# -Power.net
KiCad netlist of a schematic drawn in Altium Designer
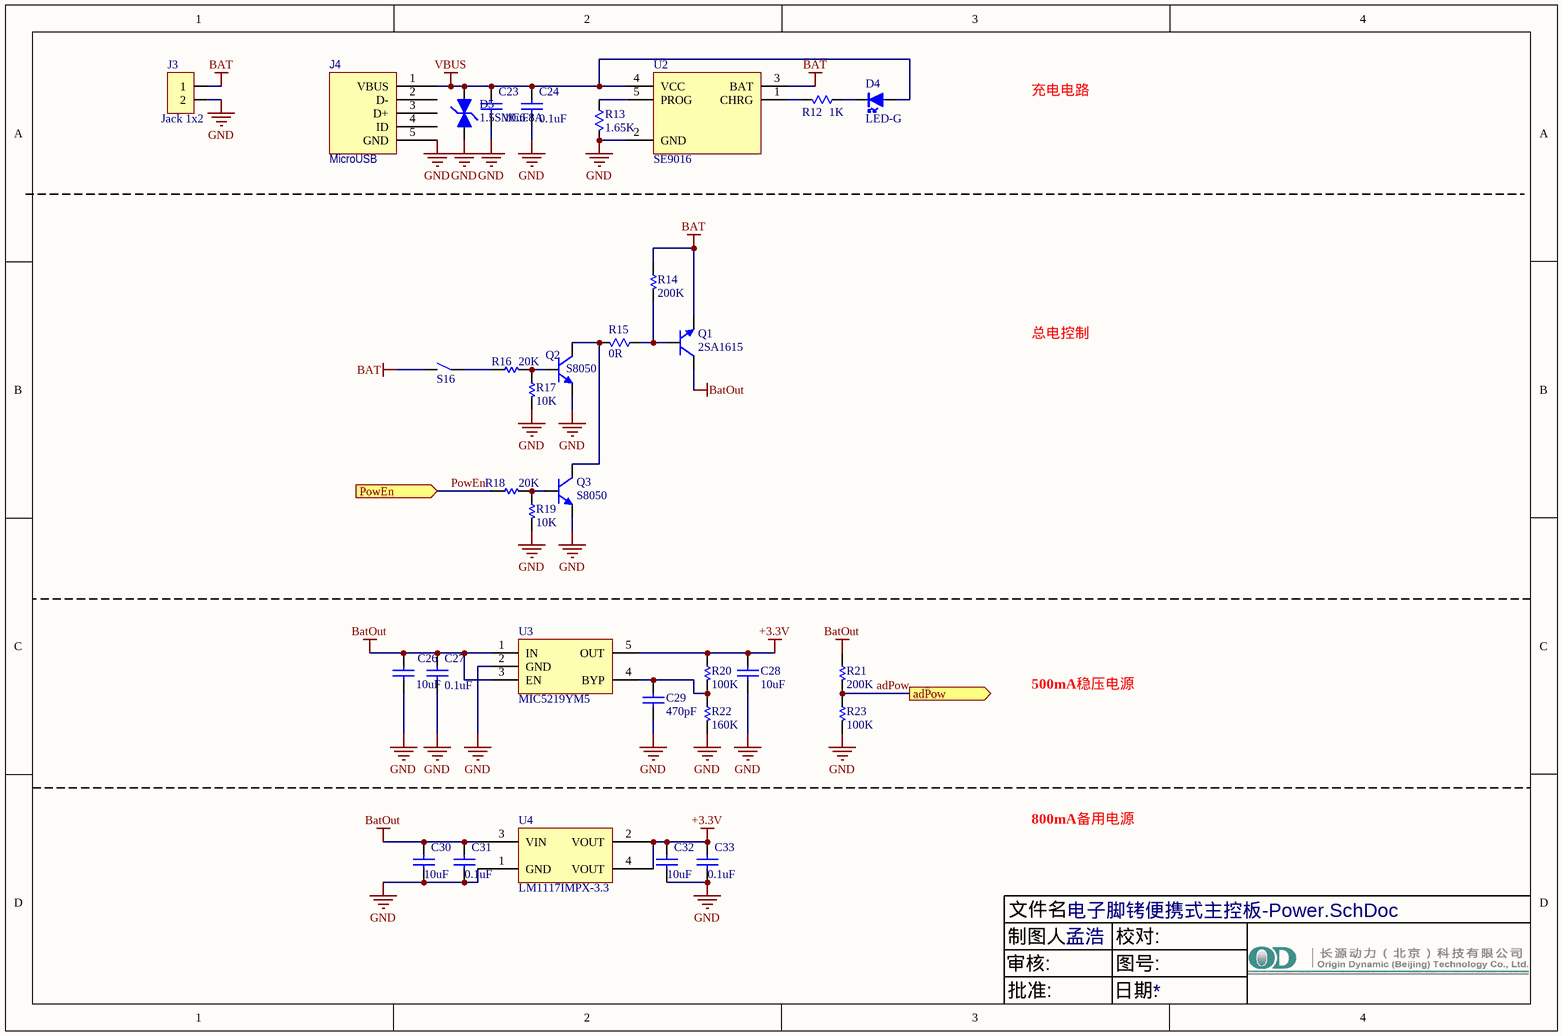
[diagram p0: 电子脚铐便携式主控板-Power.SchDoc]

(export (version "E")
  (design (tool "Eeschema 10.0.6"))
  (components
    (comp (ref "C23")
      (value "10uF")
      (footprint "C1206")
      (description "Capacitor")
      (fields (field (name "PUBLISHER") "Altium Limited"))
      (libsource (lib "Miscellaneous Devices") (part "Cap"))
    )
    (comp (ref "C24")
      (value "0.1uF")
      (footprint "C0603")
      (description "Capacitor")
      (libsource (lib "Miscellaneous Devices") (part "Cap"))
    )
    (comp (ref "C26")
      (value "10uF")
      (footprint "C0603")
      (description "CAP")
      (fields (field (name "PUBLISHER") "Altium Limited"))
      (libsource (lib "Passive Components Class") (part "CAP"))
    )
    (comp (ref "C27") (value "0.1uF") (footprint "C0603") (libsource (lib "RLCYDF") (part "Cap Semi")))
    (comp (ref "C28")
      (value "10uF")
      (footprint "C0603")
      (description "CAP")
      (fields (field (name "PUBLISHER") "Altium Limited"))
      (libsource (lib "Passive Components Class") (part "CAP"))
    )
    (comp (ref "C29")
      (value "470pF")
      (footprint "C0603")
      (description "CAP")
      (fields (field (name "PUBLISHER") "Altium Limited"))
      (libsource (lib "Passive Components Class") (part "CAP"))
    )
    (comp (ref "C30")
      (value "10uF")
      (footprint "C0603")
      (description "CAP")
      (libsource (lib "Passive Components Class") (part "CAP"))
    )
    (comp (ref "C31")
      (value "0.1uF")
      (footprint "C0603")
      (description "CAP")
      (libsource (lib "Passive Components Class") (part "CAP"))
    )
    (comp (ref "C32")
      (value "10uF")
      (footprint "C0603")
      (description "CAP")
      (libsource (lib "Passive Components Class") (part "CAP"))
    )
    (comp (ref "C33")
      (value "0.1uF")
      (footprint "C0603")
      (description "CAP")
      (libsource (lib "Passive Components Class") (part "CAP"))
    )
    (comp (ref "D4")
      (value "LED-G")
      (footprint "LED0805")
      (libsource (lib "Passive Components Class") (part "LED"))
    )
    (comp (ref "D5") (value "1.5SMC6.8A") (footprint "SMC") (libsource (lib "RLCYDF") (part "Diode-TVS")))
    (comp (ref "J3")
      (value "Jack 1x2")
      (footprint "DF13-2P-1.25V")
      (description "插座")
      (libsource (lib "Connector") (part "Jack 1x2"))
    )
    (comp (ref "J4") (value "MicroUSB") (footprint "MICRO-USB") (libsource (lib "JLib") (part "MicroUSB")))
    (comp (ref "Q1") (value "2SA1615") (footprint "TO-252") (libsource (lib "ArmArmor") (part "MJD122")))
    (comp (ref "Q2")
      (value "S8050")
      (footprint "SOT-23")
      (description "NPN triode, 0.5A Max")
      (libsource (lib "RLCYDF") (part "S8050"))
    )
    (comp (ref "Q3")
      (value "S8050")
      (footprint "SOT-23")
      (description "NPN triode, 0.5A Max")
      (libsource (lib "RLCYDF") (part "S8050"))
    )
    (comp (ref "R12")
      (value "1K")
      (footprint "R0603")
      (description "Resistor")
      (fields (field (name "PUBLISHER") "Altium Limited"))
      (libsource (lib "UP-Robot") (part "Res"))
    )
    (comp (ref "R13")
      (value "1.65K")
      (footprint "R0603")
      (description "Resistor")
      (fields (field (name "PUBLISHER") "Altium Limited"))
      (libsource (lib "Temp") (part "Res"))
    )
    (comp (ref "R14") (value "200K") (footprint "R0603") (libsource (lib "RLCYDF") (part "Res")))
    (comp (ref "R15")
      (value "0R")
      (footprint "R0603")
      (description "Resistor")
      (fields (field (name "PUBLISHER") "Altium Limited"))
      (libsource (lib "Passive Components Class") (part "RES"))
    )
    (comp (ref "R16") (value "20K") (footprint "R0603") (libsource (lib "RLCYDF") (part "Res")))
    (comp (ref "R17") (value "10K") (footprint "R0603") (libsource (lib "RLCYDF") (part "Res")))
    (comp (ref "R18") (value "20K") (footprint "R0603") (libsource (lib "RLCYDF") (part "Res")))
    (comp (ref "R19") (value "10K") (footprint "R0603") (libsource (lib "RLCYDF") (part "Res")))
    (comp (ref "R20") (value "100K") (footprint "R0603") (libsource (lib "RLCYDF") (part "Res")))
    (comp (ref "R21") (value "200K") (footprint "R0603") (libsource (lib "RLCYDF") (part "Res")))
    (comp (ref "R22") (value "160K") (footprint "R0603") (libsource (lib "RLCYDF") (part "Res")))
    (comp (ref "R23") (value "100K") (footprint "R0603") (libsource (lib "RLCYDF") (part "Res")))
    (comp (ref "S16") (value "Switch") (footprint "SWITCH-H") (libsource (lib "Connector") (part "Sw")))
    (comp (ref "U2") (value "SE9016") (footprint "SOT-23-5") (libsource (lib "chip") (part "SE9016")))
    (comp (ref "U3") (value "MIC5219YM5") (footprint "SOT-23-5") (libsource (lib "Power") (part "MIC5205")))
    (comp (ref "U4")
      (value "LM1117IMPX-3.3")
      (footprint "SOT-223")
      (description "800mA Low-Dropout Linear Regulator")
      (libsource (lib "Power Management Class") (part "AMS1117"))
    )
  )
  (nets
    (net (code "1") (name "+3.3V") (class "Default")
      (node (ref "C28") (pin "1") (pinfunction "1_1") (pintype "passive"))
      (node (ref "C32") (pin "1") (pinfunction "1_1") (pintype "passive"))
      (node (ref "C33") (pin "1") (pinfunction "1_1") (pintype "passive"))
      (node (ref "R20") (pin "1") (pinfunction "1_1") (pintype "passive"))
      (node (ref "U3") (pin "5") (pinfunction "OUT_5") (pintype "passive"))
      (node (ref "U4") (pin "2") (pinfunction "VOUT_2") (pintype "passive"))
      (node (ref "U4") (pin "4") (pinfunction "VOUT_4") (pintype "passive"))
    )
    (net (code "2") (name "/PowEn") (class "Default")
      (node (ref "R18") (pin "1") (pinfunction "1_1") (pintype "passive"))
    )
    (net (code "3") (name "/adPow") (class "Default")
      (node (ref "R21") (pin "2") (pinfunction "2_2") (pintype "passive"))
      (node (ref "R23") (pin "1") (pinfunction "1_1") (pintype "passive"))
    )
    (net (code "4") (name "BAT") (class "Default")
      (node (ref "J3") (pin "1") (pinfunction "1_1") (pintype "passive"))
      (node (ref "Q1") (pin "3") (pinfunction "E_3") (pintype "passive"))
      (node (ref "R14") (pin "1") (pinfunction "1_1") (pintype "passive"))
      (node (ref "S16") (pin "2") (pinfunction "2_2") (pintype "passive"))
      (node (ref "U2") (pin "3") (pinfunction "BAT_3") (pintype "passive"))
    )
    (net (code "5") (name "BatOut") (class "Default")
      (node (ref "C26") (pin "1") (pinfunction "1_1") (pintype "passive"))
      (node (ref "C27") (pin "2") (pinfunction "2_2") (pintype "passive"))
      (node (ref "C30") (pin "1") (pinfunction "1_1") (pintype "passive"))
      (node (ref "C31") (pin "1") (pinfunction "1_1") (pintype "passive"))
      (node (ref "Q1") (pin "2") (pinfunction "C_2") (pintype "passive"))
      (node (ref "R21") (pin "1") (pinfunction "1_1") (pintype "passive"))
      (node (ref "U3") (pin "1") (pinfunction "IN_1") (pintype "passive"))
      (node (ref "U3") (pin "3") (pinfunction "EN_3") (pintype "passive"))
      (node (ref "U4") (pin "3") (pinfunction "VIN_3") (pintype "passive"))
    )
    (net (code "6") (name "GND") (class "Default")
      (node (ref "C23") (pin "2") (pinfunction "2_2") (pintype "passive"))
      (node (ref "C24") (pin "2") (pinfunction "2_2") (pintype "passive"))
      (node (ref "C26") (pin "2") (pinfunction "2_2") (pintype "passive"))
      (node (ref "C27") (pin "1") (pinfunction "1_1") (pintype "passive"))
      (node (ref "C28") (pin "2") (pinfunction "2_2") (pintype "passive"))
      (node (ref "C29") (pin "2") (pinfunction "2_2") (pintype "passive"))
      (node (ref "C30") (pin "2") (pinfunction "2_2") (pintype "passive"))
      (node (ref "C31") (pin "2") (pinfunction "2_2") (pintype "passive"))
      (node (ref "C32") (pin "2") (pinfunction "2_2") (pintype "passive"))
      (node (ref "C33") (pin "2") (pinfunction "2_2") (pintype "passive"))
      (node (ref "D5") (pin "2") (pinfunction "K_2") (pintype "passive"))
      (node (ref "J3") (pin "2") (pinfunction "2_2") (pintype "passive"))
      (node (ref "J4") (pin "5") (pinfunction "GND_5") (pintype "passive"))
      (node (ref "Q2") (pin "2") (pinfunction "e_2") (pintype "passive"))
      (node (ref "Q3") (pin "2") (pinfunction "e_2") (pintype "passive"))
      (node (ref "R13") (pin "1") (pinfunction "1_1") (pintype "passive"))
      (node (ref "R17") (pin "2") (pinfunction "2_2") (pintype "passive"))
      (node (ref "R19") (pin "2") (pinfunction "2_2") (pintype "passive"))
      (node (ref "R22") (pin "2") (pinfunction "2_2") (pintype "passive"))
      (node (ref "R23") (pin "2") (pinfunction "2_2") (pintype "passive"))
      (node (ref "U2") (pin "2") (pinfunction "GND_2") (pintype "passive"))
      (node (ref "U3") (pin "2") (pinfunction "GND_2") (pintype "passive"))
      (node (ref "U4") (pin "1") (pinfunction "GND_1") (pintype "passive"))
    )
    (net (code "7") (name "Net-(D4-K)") (class "Default")
      (node (ref "D4") (pin "2") (pinfunction "K_2") (pintype "passive"))
      (node (ref "R12") (pin "2") (pinfunction "2_2") (pintype "passive"))
    )
    (net (code "8") (name "Net-(Q1-B)") (class "Default")
      (node (ref "Q1") (pin "1") (pinfunction "B_1") (pintype "passive"))
      (node (ref "R14") (pin "2") (pinfunction "2_2") (pintype "passive"))
      (node (ref "R15") (pin "1") (pinfunction "1_1") (pintype "passive"))
    )
    (net (code "9") (name "Net-(Q2-b)") (class "Default")
      (node (ref "Q2") (pin "1") (pinfunction "b_1") (pintype "passive"))
      (node (ref "R16") (pin "2") (pinfunction "2_2") (pintype "passive"))
      (node (ref "R17") (pin "1") (pinfunction "1_1") (pintype "passive"))
    )
    (net (code "10") (name "Net-(Q2-c)") (class "Default")
      (node (ref "Q2") (pin "3") (pinfunction "c_3") (pintype "passive"))
      (node (ref "Q3") (pin "3") (pinfunction "c_3") (pintype "passive"))
      (node (ref "R15") (pin "2") (pinfunction "2_2") (pintype "passive"))
    )
    (net (code "11") (name "Net-(Q3-b)") (class "Default")
      (node (ref "Q3") (pin "1") (pinfunction "b_1") (pintype "passive"))
      (node (ref "R18") (pin "2") (pinfunction "2_2") (pintype "passive"))
      (node (ref "R19") (pin "1") (pinfunction "1_1") (pintype "passive"))
    )
    (net (code "12") (name "Net-(R16-Pad1)") (class "Default")
      (node (ref "R16") (pin "1") (pinfunction "1_1") (pintype "passive"))
      (node (ref "S16") (pin "1") (pinfunction "1_1") (pintype "passive"))
    )
    (net (code "13") (name "Net-(U2-CHRG)") (class "Default")
      (node (ref "R12") (pin "1") (pinfunction "1_1") (pintype "passive"))
      (node (ref "U2") (pin "1") (pinfunction "CHRG_1") (pintype "passive"))
    )
    (net (code "14") (name "Net-(U2-PROG)") (class "Default")
      (node (ref "R13") (pin "2") (pinfunction "2_2") (pintype "passive"))
      (node (ref "U2") (pin "5") (pinfunction "PROG_5") (pintype "passive"))
    )
    (net (code "15") (name "Net-(U3-BYP)") (class "Default")
      (node (ref "C29") (pin "1") (pinfunction "1_1") (pintype "passive"))
      (node (ref "R20") (pin "2") (pinfunction "2_2") (pintype "passive"))
      (node (ref "R22") (pin "1") (pinfunction "1_1") (pintype "passive"))
      (node (ref "U3") (pin "4") (pinfunction "BYP_4") (pintype "passive"))
    )
    (net (code "16") (name "VBUS") (class "Default")
      (node (ref "C23") (pin "1") (pinfunction "1_1") (pintype "passive"))
      (node (ref "C24") (pin "1") (pinfunction "1_1") (pintype "passive"))
      (node (ref "D4") (pin "1") (pinfunction "A_1") (pintype "passive"))
      (node (ref "D5") (pin "1") (pinfunction "A_1") (pintype "passive"))
      (node (ref "J4") (pin "1") (pinfunction "VBUS_1") (pintype "passive"))
      (node (ref "U2") (pin "4") (pinfunction "VCC_4") (pintype "passive"))
    )
    (net (code "17") (name "unconnected-(J4-D+-Pad3)") (class "Default")
      (node (ref "J4") (pin "3") (pinfunction "D+_3") (pintype "passive"))
    )
    (net (code "18") (name "unconnected-(J4-D--Pad2)") (class "Default")
      (node (ref "J4") (pin "2") (pinfunction "D-_2") (pintype "passive"))
    )
    (net (code "19") (name "unconnected-(J4-ID-Pad4)") (class "Default")
      (node (ref "J4") (pin "4") (pinfunction "ID_4") (pintype "passive"))
    )
  )
)
